# 1S_BATTERY_CHARGER_SCH.net
KiCad netlist of a schematic drawn in Altium Designer
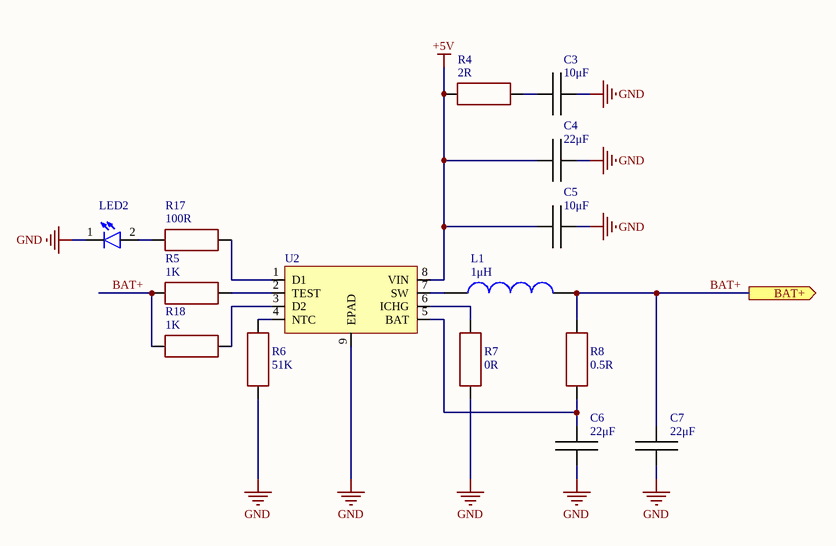
[diagram p0: 1S_BATTERY_CHARGER_SCH.SchDoc]

(export (version "E")
  (design (tool "Eeschema 10.0.6"))
  (components
    (comp (ref "C3")
      (value "10μF")
      (footprint "CAP: 0603")
      (fields (field (name "VOLTAGE") "??V") (field (name "Comment") "Cap_0603"))
      (libsource (lib "capacitor") (part "Cap_0603"))
    )
    (comp (ref "C4")
      (value "22μF")
      (footprint "CAP: 0603")
      (fields (field (name "VOLTAGE") "??V") (field (name "Comment") "Cap_0603"))
      (libsource (lib "capacitor") (part "Cap_0603"))
    )
    (comp (ref "C5")
      (value "10μF")
      (footprint "CAP: 0603")
      (fields (field (name "VOLTAGE") "??V") (field (name "Comment") "Cap_0603"))
      (libsource (lib "capacitor") (part "Cap_0603"))
    )
    (comp (ref "C6")
      (value "22μF")
      (footprint "CAP: 0603")
      (fields (field (name "VOLTAGE") "??V") (field (name "Comment") "Cap_0603"))
      (libsource (lib "capacitor") (part "Cap_0603"))
    )
    (comp (ref "C7")
      (value "22μF")
      (footprint "CAP: 0603")
      (fields (field (name "VOLTAGE") "??V") (field (name "Comment") "Cap_0603"))
      (libsource (lib "capacitor") (part "Cap_0603"))
    )
    (comp (ref "L1")
      (value "1μH")
      (footprint "CDRH74")
      (description "SMD Power Inductor")
      (fields (field (name "MANUFACTURER") "SUMIDA") (field (name "Comment") "CDRH74"))
      (libsource (lib "MY_INT_LIB") (part "CDRH74"))
    )
    (comp (ref "LED2")
      (value "LED_0603")
      (footprint "LED_0603")
      (libsource (lib "MY_INT_LIB") (part "LED_0603"))
    )
    (comp (ref "R4")
      (value "2R")
      (footprint "RES: 0603")
      (fields (field (name "TOLERANCE") "±5%") (field (name "Comment") "Resistor_0603"))
      (libsource (lib "resistor") (part "Resistor_0603"))
    )
    (comp (ref "R5")
      (value "1K")
      (footprint "RES: 0603")
      (fields (field (name "TOLERANCE") "±5%") (field (name "Comment") "Resistor_0603"))
      (libsource (lib "") (part "Resistor_0603_1"))
    )
    (comp (ref "R6")
      (value "51K")
      (footprint "RES: 0603")
      (fields (field (name "TOLERANCE") "±5%") (field (name "Comment") "Resistor_0603"))
      (libsource (lib "resistor") (part "Resistor_0603"))
    )
    (comp (ref "R7")
      (value "0R")
      (footprint "RES: 0603")
      (fields (field (name "TOLERANCE") "±5%") (field (name "Comment") "Resistor_0603"))
      (libsource (lib "") (part "Resistor_0603_2"))
    )
    (comp (ref "R8")
      (value "0.5R")
      (footprint "RES: 0603")
      (fields (field (name "TOLERANCE") "±5%") (field (name "Comment") "Resistor_0603"))
      (libsource (lib "resistor") (part "Resistor_0603"))
    )
    (comp (ref "R17")
      (value "100R")
      (footprint "RES: 0603")
      (fields (field (name "TOLERANCE") "±5%") (field (name "Comment") "Resistor_0603"))
      (libsource (lib "resistor") (part "Resistor_0603"))
    )
    (comp (ref "R18")
      (value "1K")
      (footprint "RES: 0603")
      (fields (field (name "TOLERANCE") "±5%") (field (name "Comment") "Resistor_0603"))
      (libsource (lib "") (part "Resistor_0603_1"))
    )
    (comp (ref "U2")
      (value "IP2312")
      (footprint "ESOP-8")
      (description "1s charge module")
      (fields (field (name "MANUFACTURER") "INJOINIC"))
      (libsource (lib "MY_INT_LIB") (part "IP2312"))
    )
  )
  (nets
    (net (code "1") (name "+5V") (class "Default")
      (node (ref "C4") (pin "2") (pinfunction "2_2") (pintype "passive"))
      (node (ref "C5") (pin "2") (pinfunction "2_2") (pintype "passive"))
      (node (ref "R4") (pin "1") (pinfunction "1_1") (pintype "passive"))
      (node (ref "U2") (pin "8") (pinfunction "VIN_8") (pintype "passive"))
    )
    (net (code "2") (name "/BAT+") (class "Default")
      (node (ref "C7") (pin "1") (pinfunction "1_1") (pintype "passive"))
      (node (ref "L1") (pin "1") (pinfunction "1_1") (pintype "passive"))
      (node (ref "R18") (pin "1") (pinfunction "1_1") (pintype "passive"))
      (node (ref "R5") (pin "1") (pinfunction "1_1") (pintype "passive"))
      (node (ref "R8") (pin "2") (pinfunction "2_2") (pintype "passive"))
    )
    (net (code "3") (name "GND") (class "Default")
      (node (ref "C3") (pin "1") (pinfunction "1_1") (pintype "passive"))
      (node (ref "C4") (pin "1") (pinfunction "1_1") (pintype "passive"))
      (node (ref "C5") (pin "1") (pinfunction "1_1") (pintype "passive"))
      (node (ref "C6") (pin "2") (pinfunction "2_2") (pintype "passive"))
      (node (ref "C7") (pin "2") (pinfunction "2_2") (pintype "passive"))
      (node (ref "LED2") (pin "1") (pintype "passive"))
      (node (ref "R6") (pin "1") (pinfunction "1_1") (pintype "passive"))
      (node (ref "R7") (pin "2") (pinfunction "2_2") (pintype "passive"))
      (node (ref "U2") (pin "9") (pinfunction "EPAD_9") (pintype "passive"))
    )
    (net (code "4") (name "Net-(C3-Pad2)") (class "Default")
      (node (ref "C3") (pin "2") (pinfunction "2_2") (pintype "passive"))
      (node (ref "R4") (pin "2") (pinfunction "2_2") (pintype "passive"))
    )
    (net (code "5") (name "Net-(LED2-Pad2)") (class "Default")
      (node (ref "LED2") (pin "2") (pintype "passive"))
      (node (ref "R17") (pin "1") (pinfunction "1_1") (pintype "passive"))
    )
    (net (code "6") (name "Net-(U2-BAT)") (class "Default")
      (node (ref "C6") (pin "1") (pinfunction "1_1") (pintype "passive"))
      (node (ref "R8") (pin "1") (pinfunction "1_1") (pintype "passive"))
      (node (ref "U2") (pin "5") (pinfunction "BAT_5") (pintype "passive"))
    )
    (net (code "7") (name "Net-(U2-D1)") (class "Default")
      (node (ref "R17") (pin "2") (pinfunction "2_2") (pintype "passive"))
      (node (ref "U2") (pin "1") (pinfunction "D1_1") (pintype "passive"))
    )
    (net (code "8") (name "Net-(U2-D2)") (class "Default")
      (node (ref "R18") (pin "2") (pinfunction "2_2") (pintype "passive"))
      (node (ref "U2") (pin "3") (pinfunction "D2_3") (pintype "passive"))
    )
    (net (code "9") (name "Net-(U2-ICHG)") (class "Default")
      (node (ref "R7") (pin "1") (pinfunction "1_1") (pintype "passive"))
      (node (ref "U2") (pin "6") (pinfunction "ICHG_6") (pintype "passive"))
    )
    (net (code "10") (name "Net-(U2-NTC)") (class "Default")
      (node (ref "R6") (pin "2") (pinfunction "2_2") (pintype "passive"))
      (node (ref "U2") (pin "4") (pinfunction "NTC_4") (pintype "passive"))
    )
    (net (code "11") (name "Net-(U2-SW)") (class "Default")
      (node (ref "L1") (pin "2") (pinfunction "2_2") (pintype "passive"))
      (node (ref "U2") (pin "7") (pinfunction "SW_7") (pintype "passive"))
    )
    (net (code "12") (name "Net-(U2-TEST)") (class "Default")
      (node (ref "R5") (pin "2") (pinfunction "2_2") (pintype "passive"))
      (node (ref "U2") (pin "2") (pinfunction "TEST_2") (pintype "passive"))
    )
  )
)
